# 4current_2te.net
KiCad netlist of a schematic drawn in EAGLE
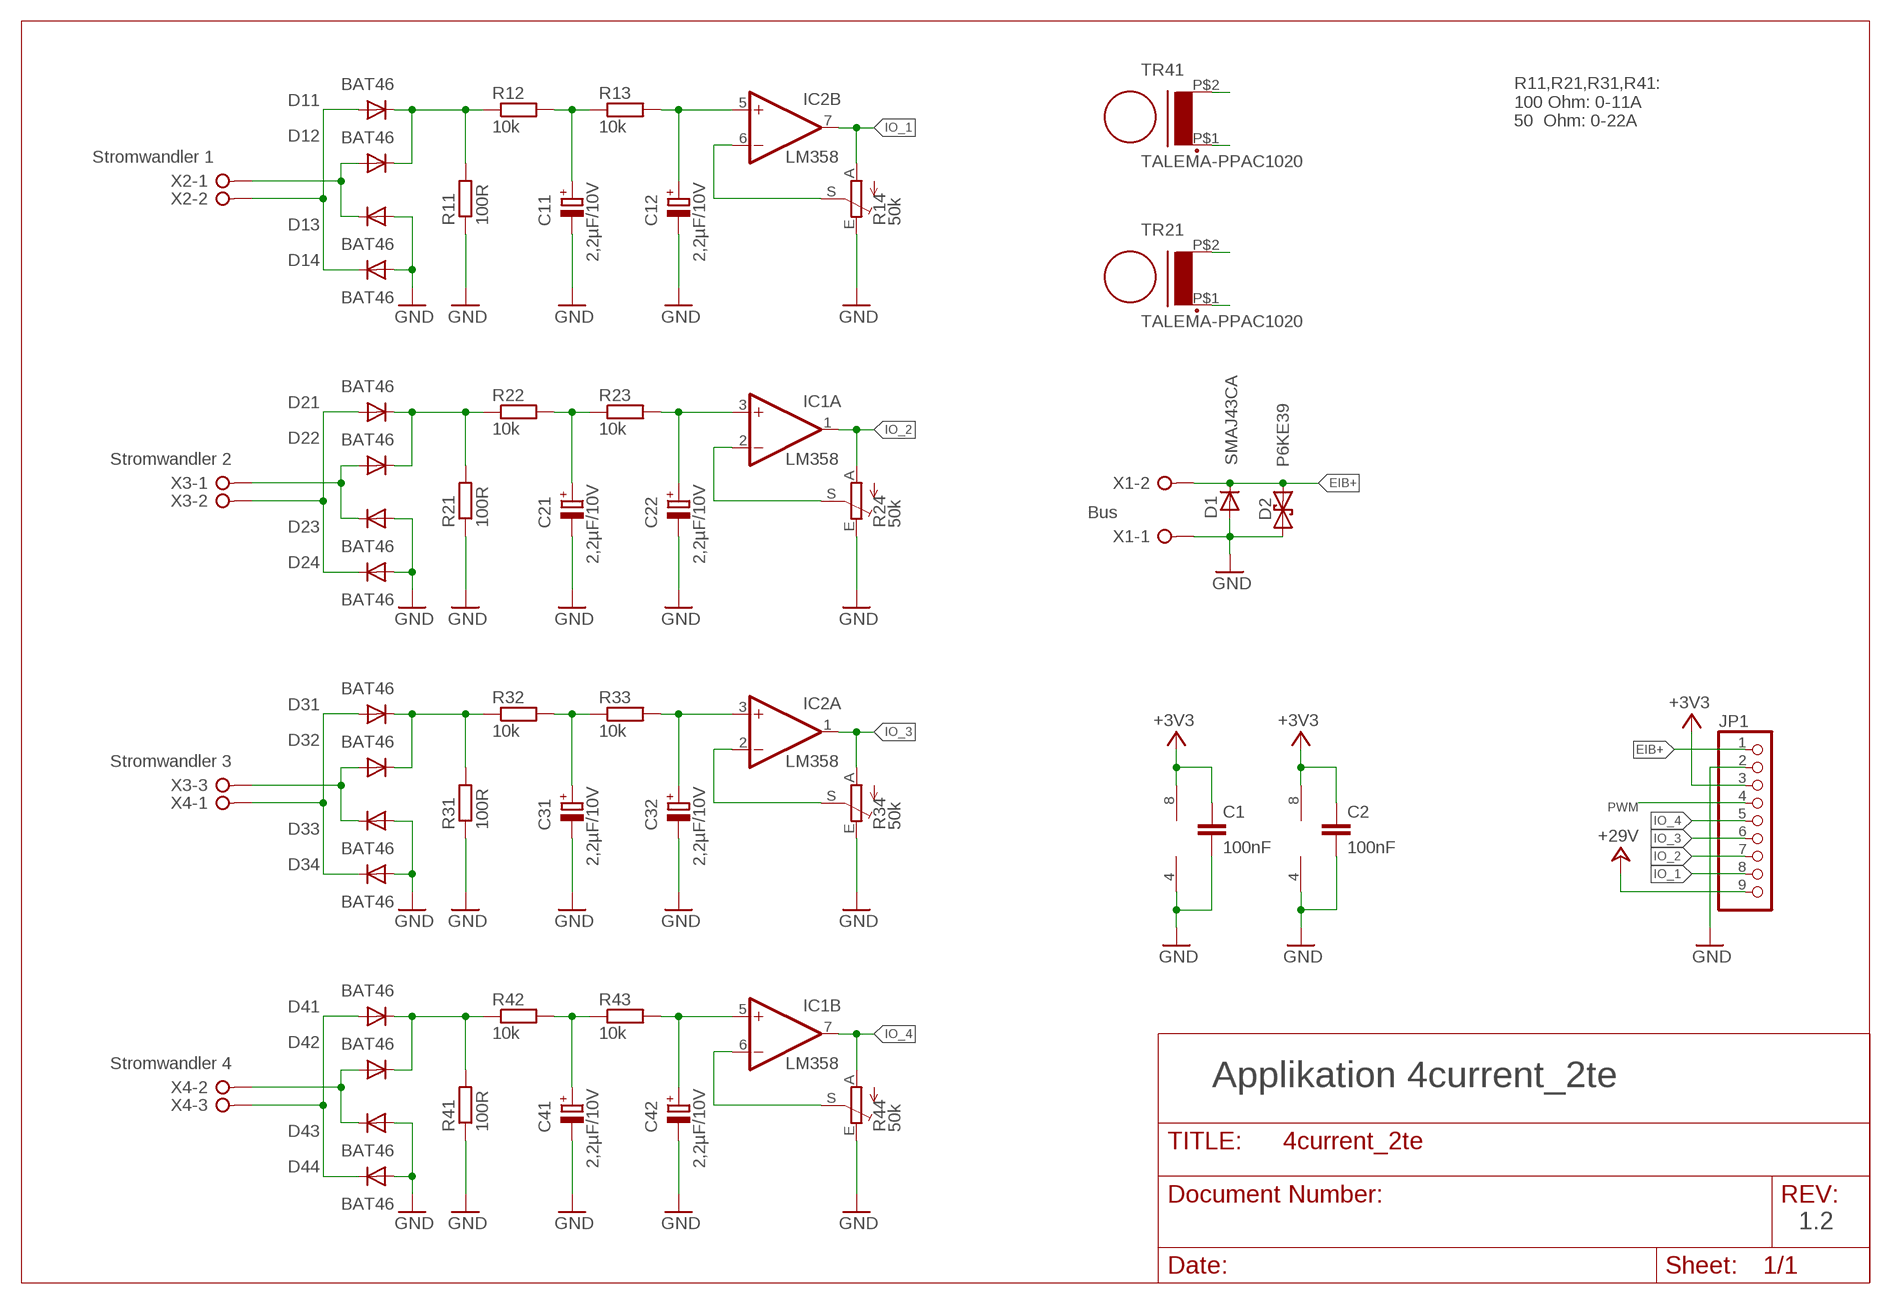
[diagram p0: schematic, sheet 1]

(export (version "E")
  (design (tool "Eeschema 10.0.6"))
  (components
    (comp (ref "C1")
      (value "100nF")
      (footprint "eagle-import:C025-024X044")
      (libsource (lib "eagle-import") (part "C-EU025-024X044"))
    )
    (comp (ref "C2")
      (value "100nF")
      (footprint "eagle-import:C025-024X044")
      (libsource (lib "eagle-import") (part "C-EU025-024X044"))
    )
    (comp (ref "C11")
      (value "2,2µF/10V")
      (footprint "eagle-import:E2-5")
      (libsource (lib "eagle-import") (part "CPOL-EUE2-5"))
    )
    (comp (ref "C12")
      (value "2,2µF/10V")
      (footprint "eagle-import:E2-5")
      (libsource (lib "eagle-import") (part "CPOL-EUE2-5"))
    )
    (comp (ref "C21")
      (value "2,2µF/10V")
      (footprint "eagle-import:E2-5")
      (libsource (lib "eagle-import") (part "CPOL-EUE2-5"))
    )
    (comp (ref "C22")
      (value "2,2µF/10V")
      (footprint "eagle-import:E2-5")
      (libsource (lib "eagle-import") (part "CPOL-EUE2-5"))
    )
    (comp (ref "C31")
      (value "2,2µF/10V")
      (footprint "eagle-import:E2-5")
      (libsource (lib "eagle-import") (part "CPOL-EUE2-5"))
    )
    (comp (ref "C32")
      (value "2,2µF/10V")
      (footprint "eagle-import:E2-5")
      (libsource (lib "eagle-import") (part "CPOL-EUE2-5"))
    )
    (comp (ref "C41")
      (value "2,2µF/10V")
      (footprint "eagle-import:E2-5")
      (libsource (lib "eagle-import") (part "CPOL-EUE2-5"))
    )
    (comp (ref "C42")
      (value "2,2µF/10V")
      (footprint "eagle-import:E2-5")
      (libsource (lib "eagle-import") (part "CPOL-EUE2-5"))
    )
    (comp (ref "D1")
      (value "SMAJ43CA")
      (footprint "eagle-import:SOD87")
      (libsource (lib "eagle-import") (part "D-SOD-87"))
    )
    (comp (ref "D2")
      (value "P6KE39")
      (footprint "eagle-import:DO41-7")
      (libsource (lib "eagle-import") (part "P6KEXXCDO41-7"))
    )
    (comp (ref "D11")
      (value "BAT46")
      (footprint "eagle-import:DO35-7")
      (libsource (lib "eagle-import") (part "1N4148DO35-7"))
    )
    (comp (ref "D12")
      (value "BAT46")
      (footprint "eagle-import:DO35-7")
      (libsource (lib "eagle-import") (part "1N4148DO35-7"))
    )
    (comp (ref "D13")
      (value "BAT46")
      (footprint "eagle-import:DO35-7")
      (libsource (lib "eagle-import") (part "1N4148DO35-7"))
    )
    (comp (ref "D14")
      (value "BAT46")
      (footprint "eagle-import:DO35-7")
      (libsource (lib "eagle-import") (part "1N4148DO35-7"))
    )
    (comp (ref "D21")
      (value "BAT46")
      (footprint "eagle-import:DO35-7")
      (libsource (lib "eagle-import") (part "1N4148DO35-7"))
    )
    (comp (ref "D22")
      (value "BAT46")
      (footprint "eagle-import:DO35-7")
      (libsource (lib "eagle-import") (part "1N4148DO35-7"))
    )
    (comp (ref "D23")
      (value "BAT46")
      (footprint "eagle-import:DO35-7")
      (libsource (lib "eagle-import") (part "1N4148DO35-7"))
    )
    (comp (ref "D24")
      (value "BAT46")
      (footprint "eagle-import:DO35-7")
      (libsource (lib "eagle-import") (part "1N4148DO35-7"))
    )
    (comp (ref "D31")
      (value "BAT46")
      (footprint "eagle-import:DO35-7")
      (libsource (lib "eagle-import") (part "1N4148DO35-7"))
    )
    (comp (ref "D32")
      (value "BAT46")
      (footprint "eagle-import:DO35-7")
      (libsource (lib "eagle-import") (part "1N4148DO35-7"))
    )
    (comp (ref "D33")
      (value "BAT46")
      (footprint "eagle-import:DO35-7")
      (libsource (lib "eagle-import") (part "1N4148DO35-7"))
    )
    (comp (ref "D34")
      (value "BAT46")
      (footprint "eagle-import:DO35-7")
      (libsource (lib "eagle-import") (part "1N4148DO35-7"))
    )
    (comp (ref "D41")
      (value "BAT46")
      (footprint "eagle-import:DO35-7")
      (libsource (lib "eagle-import") (part "1N4148DO35-7"))
    )
    (comp (ref "D42")
      (value "BAT46")
      (footprint "eagle-import:DO35-7")
      (libsource (lib "eagle-import") (part "1N4148DO35-7"))
    )
    (comp (ref "D43")
      (value "BAT46")
      (footprint "eagle-import:DO35-7")
      (libsource (lib "eagle-import") (part "1N4148DO35-7"))
    )
    (comp (ref "D44")
      (value "BAT46")
      (footprint "eagle-import:DO35-7")
      (libsource (lib "eagle-import") (part "1N4148DO35-7"))
    )
    (comp (ref "IC1")
      (value "LM358")
      (footprint "eagle-import:DIL08")
      (libsource (lib "eagle-import") (part "LM358N"))
    )
    (comp (ref "IC2")
      (value "LM358")
      (footprint "eagle-import:DIL08")
      (libsource (lib "eagle-import") (part "LM358N"))
    )
    (comp (ref "JP1")
      (value "PINHD-1X9")
      (footprint "eagle-import:1X09")
      (libsource (lib "eagle-import") (part "PINHD-1X9"))
    )
    (comp (ref "R11")
      (value "100R")
      (footprint "eagle-import:0204_7")
      (libsource (lib "eagle-import") (part "R-EU_0204/7"))
    )
    (comp (ref "R12")
      (value "10k")
      (footprint "eagle-import:0204_7")
      (libsource (lib "eagle-import") (part "R-EU_0204/7"))
    )
    (comp (ref "R13")
      (value "10k")
      (footprint "eagle-import:0204_7")
      (libsource (lib "eagle-import") (part "R-EU_0204/7"))
    )
    (comp (ref "R14")
      (value "50k")
      (footprint "eagle-import:B64W")
      (libsource (lib "eagle-import") (part "TRIM_EU-B64W"))
    )
    (comp (ref "R21")
      (value "100R")
      (footprint "eagle-import:0204_7")
      (libsource (lib "eagle-import") (part "R-EU_0204/7"))
    )
    (comp (ref "R22")
      (value "10k")
      (footprint "eagle-import:0204_7")
      (libsource (lib "eagle-import") (part "R-EU_0204/7"))
    )
    (comp (ref "R23")
      (value "10k")
      (footprint "eagle-import:0204_7")
      (libsource (lib "eagle-import") (part "R-EU_0204/7"))
    )
    (comp (ref "R24")
      (value "50k")
      (footprint "eagle-import:B64W")
      (libsource (lib "eagle-import") (part "TRIM_EU-B64W"))
    )
    (comp (ref "R31")
      (value "100R")
      (footprint "eagle-import:0204_7")
      (libsource (lib "eagle-import") (part "R-EU_0204/7"))
    )
    (comp (ref "R32")
      (value "10k")
      (footprint "eagle-import:0204_7")
      (libsource (lib "eagle-import") (part "R-EU_0204/7"))
    )
    (comp (ref "R33")
      (value "10k")
      (footprint "eagle-import:0204_7")
      (libsource (lib "eagle-import") (part "R-EU_0204/7"))
    )
    (comp (ref "R34")
      (value "50k")
      (footprint "eagle-import:B64W")
      (libsource (lib "eagle-import") (part "TRIM_EU-B64W"))
    )
    (comp (ref "R41")
      (value "100R")
      (footprint "eagle-import:0204_7")
      (libsource (lib "eagle-import") (part "R-EU_0204/7"))
    )
    (comp (ref "R42")
      (value "10k")
      (footprint "eagle-import:0204_7")
      (libsource (lib "eagle-import") (part "R-EU_0204/7"))
    )
    (comp (ref "R43")
      (value "10k")
      (footprint "eagle-import:0204_7")
      (libsource (lib "eagle-import") (part "R-EU_0204/7"))
    )
    (comp (ref "R44")
      (value "50k")
      (footprint "eagle-import:B64W")
      (libsource (lib "eagle-import") (part "TRIM_EU-B64W"))
    )
    (comp (ref "TR21")
      (value "TALEMA-PPAC1020")
      (footprint "eagle-import:TALEMA_AC")
      (libsource (lib "eagle-import") (part "TALEMA-PPAC1020"))
    )
    (comp (ref "TR41")
      (value "TALEMA-PPAC1020")
      (footprint "eagle-import:TALEMA_AC")
      (libsource (lib "eagle-import") (part "TALEMA-PPAC1020"))
    )
    (comp (ref "X1")
      (value "W237-02P")
      (footprint "eagle-import:W237-132")
      (libsource (lib "eagle-import") (part "W237-02P"))
    )
    (comp (ref "X2")
      (value "W237-02P")
      (footprint "eagle-import:W237-132")
      (libsource (lib "eagle-import") (part "W237-02P"))
    )
    (comp (ref "X3")
      (value "W237-3E")
      (footprint "eagle-import:W237-3E")
      (libsource (lib "eagle-import") (part "W237-3E"))
    )
    (comp (ref "X4")
      (value "W237-3E")
      (footprint "eagle-import:W237-3E")
      (libsource (lib "eagle-import") (part "W237-3E"))
    )
  )
  (nets
    (net (code "1") (name "+3V3") (class "Default")
      (node (ref "C1") (pin "1") (pinfunction "1_1") (pintype "passive"))
      (node (ref "C2") (pin "1") (pinfunction "1_1") (pintype "passive"))
      (node (ref "IC1") (pin "8") (pinfunction "V+_8") (pintype "power_in"))
      (node (ref "IC2") (pin "8") (pinfunction "V+_8") (pintype "power_in"))
      (node (ref "JP1") (pin "3") (pinfunction "3_3") (pintype "passive"))
    )
    (net (code "2") (name "+29V") (class "Default")
      (node (ref "JP1") (pin "9") (pinfunction "9_9") (pintype "passive"))
    )
    (net (code "3") (name "/PWM") (class "Default")
      (node (ref "JP1") (pin "4") (pinfunction "4_4") (pintype "passive"))
    )
    (net (code "4") (name "EIB+") (class "Default")
      (node (ref "D1") (pin "1") (pinfunction "C_1") (pintype "passive"))
      (node (ref "D2") (pin "C") (pinfunction "2_C") (pintype "passive"))
      (node (ref "JP1") (pin "1") (pinfunction "1_1") (pintype "passive"))
      (node (ref "X1") (pin "2") (pinfunction "KL_2") (pintype "passive"))
    )
    (net (code "5") (name "GND") (class "Default")
      (node (ref "C1") (pin "2") (pinfunction "2_2") (pintype "passive"))
      (node (ref "C11") (pin "-") (pinfunction "-_-") (pintype "passive"))
      (node (ref "C12") (pin "-") (pinfunction "-_-") (pintype "passive"))
      (node (ref "C2") (pin "2") (pinfunction "2_2") (pintype "passive"))
      (node (ref "C21") (pin "-") (pinfunction "-_-") (pintype "passive"))
      (node (ref "C22") (pin "-") (pinfunction "-_-") (pintype "passive"))
      (node (ref "C31") (pin "-") (pinfunction "-_-") (pintype "passive"))
      (node (ref "C32") (pin "-") (pinfunction "-_-") (pintype "passive"))
      (node (ref "C41") (pin "-") (pinfunction "-_-") (pintype "passive"))
      (node (ref "C42") (pin "-") (pinfunction "-_-") (pintype "passive"))
      (node (ref "D1") (pin "2") (pinfunction "A_2") (pintype "passive"))
      (node (ref "D13") (pin "A") (pinfunction "A_A") (pintype "passive"))
      (node (ref "D14") (pin "A") (pinfunction "A_A") (pintype "passive"))
      (node (ref "D2") (pin "A") (pinfunction "1_A") (pintype "passive"))
      (node (ref "D23") (pin "A") (pinfunction "A_A") (pintype "passive"))
      (node (ref "D24") (pin "A") (pinfunction "A_A") (pintype "passive"))
      (node (ref "D33") (pin "A") (pinfunction "A_A") (pintype "passive"))
      (node (ref "D34") (pin "A") (pinfunction "A_A") (pintype "passive"))
      (node (ref "D43") (pin "A") (pinfunction "A_A") (pintype "passive"))
      (node (ref "D44") (pin "A") (pinfunction "A_A") (pintype "passive"))
      (node (ref "IC1") (pin "4") (pinfunction "V-_4") (pintype "power_in"))
      (node (ref "IC2") (pin "4") (pinfunction "V-_4") (pintype "power_in"))
      (node (ref "JP1") (pin "2") (pinfunction "2_2") (pintype "passive"))
      (node (ref "R11") (pin "1") (pinfunction "1_1") (pintype "passive"))
      (node (ref "R14") (pin "E") (pinfunction "E_E") (pintype "passive"))
      (node (ref "R21") (pin "1") (pinfunction "1_1") (pintype "passive"))
      (node (ref "R24") (pin "E") (pinfunction "E_E") (pintype "passive"))
      (node (ref "R31") (pin "1") (pinfunction "1_1") (pintype "passive"))
      (node (ref "R34") (pin "E") (pinfunction "E_E") (pintype "passive"))
      (node (ref "R41") (pin "1") (pinfunction "1_1") (pintype "passive"))
      (node (ref "R44") (pin "E") (pinfunction "E_E") (pintype "passive"))
      (node (ref "X1") (pin "1") (pinfunction "KL_1") (pintype "passive"))
    )
    (net (code "6") (name "IO_1") (class "Default")
      (node (ref "IC2") (pin "7") (pinfunction "OUT_7") (pintype "output"))
      (node (ref "JP1") (pin "8") (pinfunction "8_8") (pintype "passive"))
      (node (ref "R14") (pin "A") (pinfunction "A_A") (pintype "passive"))
    )
    (net (code "7") (name "IO_2") (class "Default")
      (node (ref "IC1") (pin "1") (pinfunction "OUT_1") (pintype "output"))
      (node (ref "JP1") (pin "7") (pinfunction "7_7") (pintype "passive"))
      (node (ref "R24") (pin "A") (pinfunction "A_A") (pintype "passive"))
    )
    (net (code "8") (name "IO_3") (class "Default")
      (node (ref "IC2") (pin "1") (pinfunction "OUT_1") (pintype "output"))
      (node (ref "JP1") (pin "6") (pinfunction "6_6") (pintype "passive"))
      (node (ref "R34") (pin "A") (pinfunction "A_A") (pintype "passive"))
    )
    (net (code "9") (name "IO_4") (class "Default")
      (node (ref "IC1") (pin "7") (pinfunction "OUT_7") (pintype "output"))
      (node (ref "JP1") (pin "5") (pinfunction "5_5") (pintype "passive"))
      (node (ref "R44") (pin "A") (pinfunction "A_A") (pintype "passive"))
    )
    (net (code "10") (name "Net-(C11-Pad+)") (class "Default")
      (node (ref "C11") (pin "+") (pinfunction "+_+") (pintype "passive"))
      (node (ref "R12") (pin "2") (pinfunction "2_2") (pintype "passive"))
      (node (ref "R13") (pin "1") (pinfunction "1_1") (pintype "passive"))
    )
    (net (code "11") (name "Net-(C21-Pad+)") (class "Default")
      (node (ref "C21") (pin "+") (pinfunction "+_+") (pintype "passive"))
      (node (ref "R22") (pin "2") (pinfunction "2_2") (pintype "passive"))
      (node (ref "R23") (pin "1") (pinfunction "1_1") (pintype "passive"))
    )
    (net (code "12") (name "Net-(C31-Pad+)") (class "Default")
      (node (ref "C31") (pin "+") (pinfunction "+_+") (pintype "passive"))
      (node (ref "R32") (pin "2") (pinfunction "2_2") (pintype "passive"))
      (node (ref "R33") (pin "1") (pinfunction "1_1") (pintype "passive"))
    )
    (net (code "13") (name "Net-(C41-Pad+)") (class "Default")
      (node (ref "C41") (pin "+") (pinfunction "+_+") (pintype "passive"))
      (node (ref "R42") (pin "2") (pinfunction "2_2") (pintype "passive"))
      (node (ref "R43") (pin "1") (pinfunction "1_1") (pintype "passive"))
    )
    (net (code "14") (name "Net-(D11-PadC)") (class "Default")
      (node (ref "D11") (pin "C") (pinfunction "C_C") (pintype "passive"))
      (node (ref "D12") (pin "C") (pinfunction "C_C") (pintype "passive"))
      (node (ref "R11") (pin "2") (pinfunction "2_2") (pintype "passive"))
      (node (ref "R12") (pin "1") (pinfunction "1_1") (pintype "passive"))
    )
    (net (code "15") (name "Net-(D21-PadC)") (class "Default")
      (node (ref "D21") (pin "C") (pinfunction "C_C") (pintype "passive"))
      (node (ref "D22") (pin "C") (pinfunction "C_C") (pintype "passive"))
      (node (ref "R21") (pin "2") (pinfunction "2_2") (pintype "passive"))
      (node (ref "R22") (pin "1") (pinfunction "1_1") (pintype "passive"))
    )
    (net (code "16") (name "Net-(D31-PadC)") (class "Default")
      (node (ref "D31") (pin "C") (pinfunction "C_C") (pintype "passive"))
      (node (ref "D32") (pin "C") (pinfunction "C_C") (pintype "passive"))
      (node (ref "R31") (pin "2") (pinfunction "2_2") (pintype "passive"))
      (node (ref "R32") (pin "1") (pinfunction "1_1") (pintype "passive"))
    )
    (net (code "17") (name "Net-(D41-PadC)") (class "Default")
      (node (ref "D41") (pin "C") (pinfunction "C_C") (pintype "passive"))
      (node (ref "D42") (pin "C") (pinfunction "C_C") (pintype "passive"))
      (node (ref "R41") (pin "2") (pinfunction "2_2") (pintype "passive"))
      (node (ref "R42") (pin "1") (pinfunction "1_1") (pintype "passive"))
    )
    (net (code "18") (name "Net-(IC1A-+IN)") (class "Default")
      (node (ref "C22") (pin "+") (pinfunction "+_+") (pintype "passive"))
      (node (ref "IC1") (pin "3") (pinfunction "+IN_3") (pintype "input"))
      (node (ref "R23") (pin "2") (pinfunction "2_2") (pintype "passive"))
    )
    (net (code "19") (name "Net-(IC1A--IN)") (class "Default")
      (node (ref "IC1") (pin "2") (pinfunction "-IN_2") (pintype "input"))
      (node (ref "R24") (pin "S") (pinfunction "S_S") (pintype "passive"))
    )
    (net (code "20") (name "Net-(IC1B-+IN)") (class "Default")
      (node (ref "C42") (pin "+") (pinfunction "+_+") (pintype "passive"))
      (node (ref "IC1") (pin "5") (pinfunction "+IN_5") (pintype "input"))
      (node (ref "R43") (pin "2") (pinfunction "2_2") (pintype "passive"))
    )
    (net (code "21") (name "Net-(IC1B--IN)") (class "Default")
      (node (ref "IC1") (pin "6") (pinfunction "-IN_6") (pintype "input"))
      (node (ref "R44") (pin "S") (pinfunction "S_S") (pintype "passive"))
    )
    (net (code "22") (name "Net-(IC2A-+IN)") (class "Default")
      (node (ref "C32") (pin "+") (pinfunction "+_+") (pintype "passive"))
      (node (ref "IC2") (pin "3") (pinfunction "+IN_3") (pintype "input"))
      (node (ref "R33") (pin "2") (pinfunction "2_2") (pintype "passive"))
    )
    (net (code "23") (name "Net-(IC2A--IN)") (class "Default")
      (node (ref "IC2") (pin "2") (pinfunction "-IN_2") (pintype "input"))
      (node (ref "R34") (pin "S") (pinfunction "S_S") (pintype "passive"))
    )
    (net (code "24") (name "Net-(IC2B-+IN)") (class "Default")
      (node (ref "C12") (pin "+") (pinfunction "+_+") (pintype "passive"))
      (node (ref "IC2") (pin "5") (pinfunction "+IN_5") (pintype "input"))
      (node (ref "R13") (pin "2") (pinfunction "2_2") (pintype "passive"))
    )
    (net (code "25") (name "Net-(IC2B--IN)") (class "Default")
      (node (ref "IC2") (pin "6") (pinfunction "-IN_6") (pintype "input"))
      (node (ref "R14") (pin "S") (pinfunction "S_S") (pintype "passive"))
    )
    (net (code "26") (name "Net-(X2A-KL)") (class "Default")
      (node (ref "D12") (pin "A") (pinfunction "A_A") (pintype "passive"))
      (node (ref "D13") (pin "C") (pinfunction "C_C") (pintype "passive"))
      (node (ref "X2") (pin "1") (pinfunction "KL_1") (pintype "passive"))
    )
    (net (code "27") (name "Net-(X2B-KL)") (class "Default")
      (node (ref "D11") (pin "A") (pinfunction "A_A") (pintype "passive"))
      (node (ref "D14") (pin "C") (pinfunction "C_C") (pintype "passive"))
      (node (ref "X2") (pin "2") (pinfunction "KL_2") (pintype "passive"))
    )
    (net (code "28") (name "Net-(X3A-KL)") (class "Default")
      (node (ref "D22") (pin "A") (pinfunction "A_A") (pintype "passive"))
      (node (ref "D23") (pin "C") (pinfunction "C_C") (pintype "passive"))
      (node (ref "X3") (pin "1") (pinfunction "KL_1") (pintype "passive"))
    )
    (net (code "29") (name "Net-(X3B-KL)") (class "Default")
      (node (ref "D21") (pin "A") (pinfunction "A_A") (pintype "passive"))
      (node (ref "D24") (pin "C") (pinfunction "C_C") (pintype "passive"))
      (node (ref "X3") (pin "2") (pinfunction "KL_2") (pintype "passive"))
    )
    (net (code "30") (name "Net-(X3C-KL)") (class "Default")
      (node (ref "D32") (pin "A") (pinfunction "A_A") (pintype "passive"))
      (node (ref "D33") (pin "C") (pinfunction "C_C") (pintype "passive"))
      (node (ref "X3") (pin "3") (pinfunction "KL_3") (pintype "passive"))
    )
    (net (code "31") (name "Net-(X4A-KL)") (class "Default")
      (node (ref "D31") (pin "A") (pinfunction "A_A") (pintype "passive"))
      (node (ref "D34") (pin "C") (pinfunction "C_C") (pintype "passive"))
      (node (ref "X4") (pin "1") (pinfunction "KL_1") (pintype "passive"))
    )
    (net (code "32") (name "Net-(X4B-KL)") (class "Default")
      (node (ref "D42") (pin "A") (pinfunction "A_A") (pintype "passive"))
      (node (ref "D43") (pin "C") (pinfunction "C_C") (pintype "passive"))
      (node (ref "X4") (pin "2") (pinfunction "KL_2") (pintype "passive"))
    )
    (net (code "33") (name "Net-(X4C-KL)") (class "Default")
      (node (ref "D41") (pin "A") (pinfunction "A_A") (pintype "passive"))
      (node (ref "D44") (pin "C") (pinfunction "C_C") (pintype "passive"))
      (node (ref "X4") (pin "3") (pinfunction "KL_3") (pintype "passive"))
    )
    (net (code "34") (name "unconnected-(TR21-S3-PadP$1)") (class "Default")
      (node (ref "TR21") (pin "P$1") (pinfunction "S3_P$1") (pintype "passive"))
    )
    (net (code "35") (name "unconnected-(TR21-S4-PadP$2)") (class "Default")
      (node (ref "TR21") (pin "P$2") (pinfunction "S4_P$2") (pintype "passive"))
    )
    (net (code "36") (name "unconnected-(TR41-S3-PadP$1)") (class "Default")
      (node (ref "TR41") (pin "P$1") (pinfunction "S3_P$1") (pintype "passive"))
    )
    (net (code "37") (name "unconnected-(TR41-S4-PadP$2)") (class "Default")
      (node (ref "TR41") (pin "P$2") (pinfunction "S4_P$2") (pintype "passive"))
    )
  )
)
